# rectifier_test.net
KiCad netlist of a schematic drawn in EAGLE
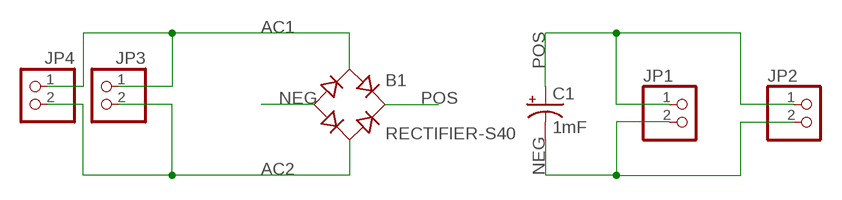
[diagram p0: schematic, sheet 1]

(export (version "E")
  (design (tool "Eeschema 10.0.6"))
  (components
    (comp (ref "B1")
      (value "RECTIFIER-S40")
      (footprint "eagle-import:TO-269AA")
      (libsource (lib "eagle-import") (part "RECTIFIER-S40"))
    )
    (comp (ref "C1")
      (value "1mF")
      (footprint "eagle-import:CPOL-RADIAL-5MM-10MM")
      (libsource (lib "eagle-import") (part "1000UF-RADIAL-5MM-25V-20%"))
    )
    (comp (ref "JP1")
      (value "PINHD-1X2")
      (footprint "eagle-import:1X02")
      (libsource (lib "eagle-import") (part "PINHD-1X2"))
    )
    (comp (ref "JP2")
      (value "PINHD-1X2")
      (footprint "eagle-import:1X02")
      (libsource (lib "eagle-import") (part "PINHD-1X2"))
    )
    (comp (ref "JP3")
      (value "PINHD-1X2")
      (footprint "eagle-import:1X02")
      (libsource (lib "eagle-import") (part "PINHD-1X2"))
    )
    (comp (ref "JP4")
      (value "PINHD-1X2")
      (footprint "eagle-import:1X02")
      (libsource (lib "eagle-import") (part "PINHD-1X2"))
    )
  )
  (nets
    (net (code "1") (name "/AC1") (class "Default")
      (node (ref "B1") (pin "AC1") (pinfunction "AC1_AC1") (pintype "passive"))
      (node (ref "JP3") (pin "1") (pinfunction "1_1") (pintype "passive"))
      (node (ref "JP4") (pin "1") (pinfunction "1_1") (pintype "passive"))
    )
    (net (code "2") (name "/AC2") (class "Default")
      (node (ref "B1") (pin "AC2") (pinfunction "AC2_AC2") (pintype "passive"))
      (node (ref "JP3") (pin "2") (pinfunction "2_2") (pintype "passive"))
      (node (ref "JP4") (pin "2") (pinfunction "2_2") (pintype "passive"))
    )
    (net (code "3") (name "/NEG") (class "Default")
      (node (ref "B1") (pin "-") (pinfunction "-_-") (pintype "passive"))
      (node (ref "C1") (pin "-") (pinfunction "-_-") (pintype "passive"))
      (node (ref "JP1") (pin "2") (pinfunction "2_2") (pintype "passive"))
      (node (ref "JP2") (pin "2") (pinfunction "2_2") (pintype "passive"))
    )
    (net (code "4") (name "/POS") (class "Default")
      (node (ref "B1") (pin "+") (pinfunction "+_+") (pintype "passive"))
      (node (ref "C1") (pin "+") (pinfunction "+_+") (pintype "passive"))
      (node (ref "JP1") (pin "1") (pinfunction "1_1") (pintype "passive"))
      (node (ref "JP2") (pin "1") (pinfunction "1_1") (pintype "passive"))
    )
  )
)
